# Superseal.net
KiCad netlist of a schematic drawn in Altium Designer
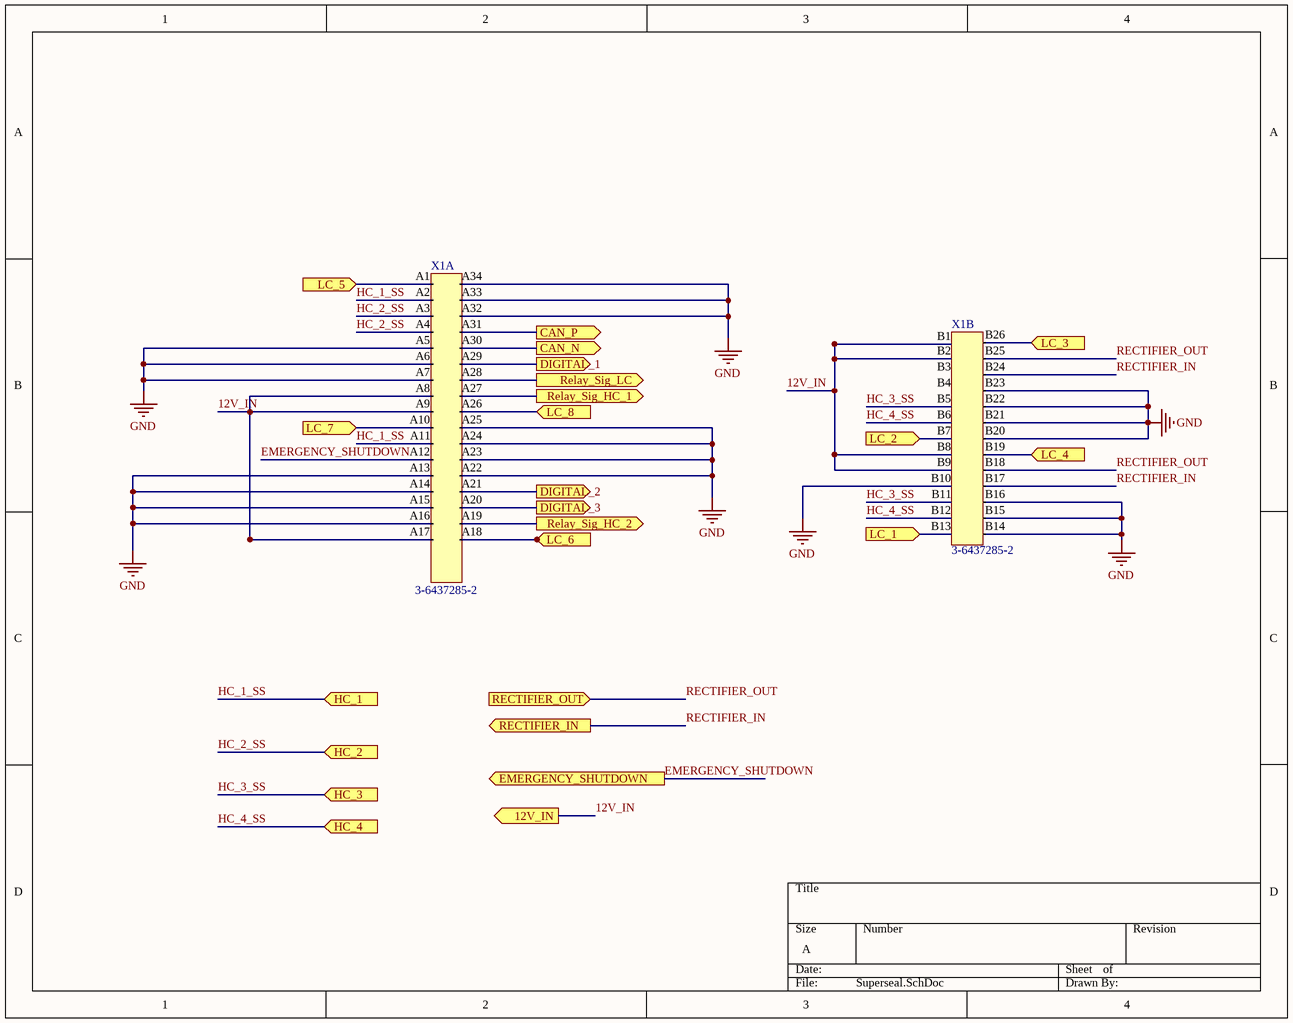
[diagram p0: Superseal.SchDoc]

(export (version "E")
  (design (tool "Eeschema 10.0.6"))
  (components
    (comp (ref "X1")
      (value "3-6437285-2")
      (footprint "SUPERSEAL 60POS 90Deg")
      (description "90 Degree")
      (libsource (lib "Altium-Lib") (part "CONN Superseal 60POS"))
    )
  )
  (nets
    (net (code "1") (name "/12V_IN") (class "Default")
      (node (ref "X1") (pin "A17") (pintype "bidirectional"))
      (node (ref "X1") (pin "A8") (pintype "bidirectional"))
      (node (ref "X1") (pin "A9") (pintype "bidirectional"))
      (node (ref "X1") (pin "B1") (pintype "bidirectional"))
      (node (ref "X1") (pin "B2") (pintype "bidirectional"))
      (node (ref "X1") (pin "B8") (pintype "bidirectional"))
      (node (ref "X1") (pin "B9") (pintype "bidirectional"))
    )
    (net (code "2") (name "/CAN_N") (class "Default") (node (ref "X1") (pin "A30") (pintype "bidirectional")))
    (net (code "3") (name "/CAN_P") (class "Default") (node (ref "X1") (pin "A31") (pintype "bidirectional")))
    (net (code "4") (name "/DIGITAL_1") (class "Default")
      (node (ref "X1") (pin "A29") (pintype "bidirectional"))
    )
    (net (code "5") (name "/DIGITAL_2") (class "Default")
      (node (ref "X1") (pin "A21") (pintype "bidirectional"))
    )
    (net (code "6") (name "/DIGITAL_3") (class "Default")
      (node (ref "X1") (pin "A20") (pintype "bidirectional"))
    )
    (net (code "7") (name "/EMERGENCY_SHUTDOWN") (class "Default")
      (node (ref "X1") (pin "A12") (pintype "bidirectional"))
    )
    (net (code "8") (name "/HC_1_SS") (class "Default")
      (node (ref "X1") (pin "A11") (pintype "bidirectional"))
      (node (ref "X1") (pin "A2") (pintype "bidirectional"))
    )
    (net (code "9") (name "/HC_2_SS") (class "Default")
      (node (ref "X1") (pin "A3") (pintype "bidirectional"))
      (node (ref "X1") (pin "A4") (pintype "bidirectional"))
    )
    (net (code "10") (name "/HC_3_SS") (class "Default")
      (node (ref "X1") (pin "B11") (pintype "bidirectional"))
      (node (ref "X1") (pin "B5") (pintype "bidirectional"))
    )
    (net (code "11") (name "/HC_4_SS") (class "Default")
      (node (ref "X1") (pin "B12") (pintype "bidirectional"))
      (node (ref "X1") (pin "B6") (pintype "bidirectional"))
    )
    (net (code "12") (name "/LC_1") (class "Default") (node (ref "X1") (pin "B13") (pintype "bidirectional")))
    (net (code "13") (name "/LC_2") (class "Default") (node (ref "X1") (pin "B7") (pintype "bidirectional")))
    (net (code "14") (name "/LC_3") (class "Default") (node (ref "X1") (pin "B26") (pintype "bidirectional")))
    (net (code "15") (name "/LC_4") (class "Default") (node (ref "X1") (pin "B19") (pintype "bidirectional")))
    (net (code "16") (name "/LC_5") (class "Default") (node (ref "X1") (pin "A1") (pintype "bidirectional")))
    (net (code "17") (name "/LC_6") (class "Default") (node (ref "X1") (pin "A18") (pintype "bidirectional")))
    (net (code "18") (name "/LC_7") (class "Default") (node (ref "X1") (pin "A10") (pintype "bidirectional")))
    (net (code "19") (name "/LC_8") (class "Default") (node (ref "X1") (pin "A26") (pintype "bidirectional")))
    (net (code "20") (name "/RECTIFIER_IN") (class "Default")
      (node (ref "X1") (pin "B17") (pintype "bidirectional"))
      (node (ref "X1") (pin "B24") (pintype "bidirectional"))
    )
    (net (code "21") (name "/RECTIFIER_OUT") (class "Default")
      (node (ref "X1") (pin "B18") (pintype "bidirectional"))
      (node (ref "X1") (pin "B25") (pintype "bidirectional"))
    )
    (net (code "22") (name "/Relay_Sig_HC_1") (class "Default")
      (node (ref "X1") (pin "A27") (pintype "bidirectional"))
    )
    (net (code "23") (name "/Relay_Sig_HC_2") (class "Default")
      (node (ref "X1") (pin "A19") (pintype "bidirectional"))
    )
    (net (code "24") (name "/Relay_Sig_LC") (class "Default")
      (node (ref "X1") (pin "A28") (pintype "bidirectional"))
    )
    (net (code "25") (name "GND") (class "Default")
      (node (ref "X1") (pin "A13") (pintype "bidirectional"))
      (node (ref "X1") (pin "A14") (pintype "bidirectional"))
      (node (ref "X1") (pin "A15") (pintype "bidirectional"))
      (node (ref "X1") (pin "A16") (pintype "bidirectional"))
      (node (ref "X1") (pin "A22") (pintype "bidirectional"))
      (node (ref "X1") (pin "A23") (pintype "bidirectional"))
      (node (ref "X1") (pin "A24") (pintype "bidirectional"))
      (node (ref "X1") (pin "A25") (pintype "bidirectional"))
      (node (ref "X1") (pin "A32") (pintype "bidirectional"))
      (node (ref "X1") (pin "A33") (pintype "bidirectional"))
      (node (ref "X1") (pin "A34") (pintype "bidirectional"))
      (node (ref "X1") (pin "A5") (pintype "bidirectional"))
      (node (ref "X1") (pin "A6") (pintype "bidirectional"))
      (node (ref "X1") (pin "A7") (pintype "bidirectional"))
      (node (ref "X1") (pin "B10") (pintype "bidirectional"))
      (node (ref "X1") (pin "B14") (pintype "bidirectional"))
      (node (ref "X1") (pin "B15") (pintype "bidirectional"))
      (node (ref "X1") (pin "B16") (pintype "bidirectional"))
      (node (ref "X1") (pin "B20") (pintype "bidirectional"))
      (node (ref "X1") (pin "B21") (pintype "bidirectional"))
      (node (ref "X1") (pin "B22") (pintype "bidirectional"))
      (node (ref "X1") (pin "B23") (pintype "bidirectional"))
    )
    (net (code "26") (name "unconnected-(X1-PadB3)") (class "Default")
      (node (ref "X1") (pin "B3") (pintype "bidirectional"))
    )
    (net (code "27") (name "unconnected-(X1-PadB4)") (class "Default")
      (node (ref "X1") (pin "B4") (pintype "bidirectional"))
    )
  )
)
